# Sheet1.net
KiCad netlist of a schematic drawn in Altium Designer
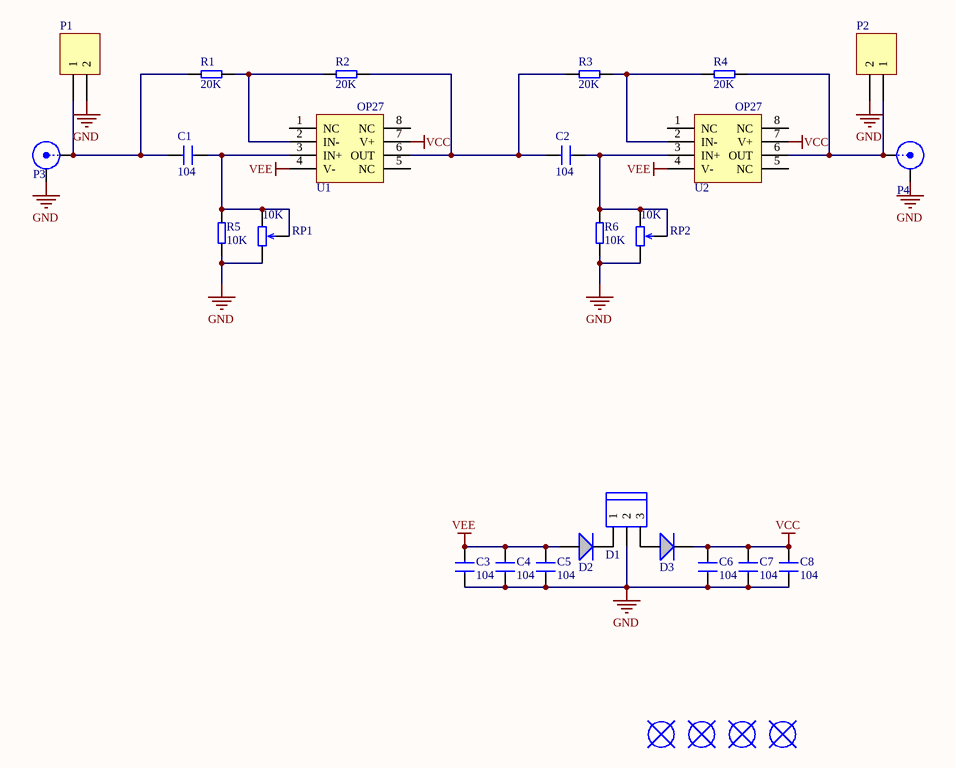
[diagram p0: 移相器Sheet1.SchDoc]

(export (version "E")
  (design (tool "Eeschema 10.0.6"))
  (components
    (comp (ref "C1") (value "104") (footprint "电容0805") (libsource (lib "自制元件库") (part "无极性电容")))
    (comp (ref "C2") (value "104") (footprint "电容0805") (libsource (lib "自制元件库") (part "无极性电容")))
    (comp (ref "C3") (value "104") (footprint "电容0805") (libsource (lib "自制元件库") (part "无极性电容")))
    (comp (ref "C4") (value "104") (footprint "电容0805") (libsource (lib "自制元件库") (part "无极性电容")))
    (comp (ref "C5") (value "104") (footprint "电容0805") (libsource (lib "自制元件库") (part "无极性电容")))
    (comp (ref "C6") (value "104") (footprint "电容0805") (libsource (lib "自制元件库") (part "无极性电容")))
    (comp (ref "C7") (value "104") (footprint "电容0805") (libsource (lib "自制元件库") (part "无极性电容")))
    (comp (ref "C8") (value "104") (footprint "电容0805") (libsource (lib "自制元件库") (part "无极性电容")))
    (comp (ref "D1") (value "接线端子") (footprint "CONN-TH_XH2.54-3P") (libsource (lib "自制元件库") (part "3P接线端子")))
    (comp (ref "D2") (value "1N4150") (footprint "DIOMELF3414N") (libsource (lib "自制元件库") (part "1N4150")))
    (comp (ref "D3") (value "1N4150") (footprint "DIOMELF3414N") (libsource (lib "自制元件库") (part "1N4150")))
    (comp (ref "G1") (value "定位孔") (footprint "定位孔") (libsource (lib "自制元件库") (part "定位孔")))
    (comp (ref "G2") (value "定位孔") (footprint "定位孔") (libsource (lib "自制元件库") (part "定位孔")))
    (comp (ref "G3") (value "定位孔") (footprint "定位孔") (libsource (lib "自制元件库") (part "定位孔")))
    (comp (ref "G4") (value "定位孔") (footprint "定位孔") (libsource (lib "自制元件库") (part "定位孔")))
    (comp (ref "P1")
      (value "Header 2")
      (footprint "HDR1X2")
      (description "Header, 2-Pin")
      (fields (field (name "PUBLISHER") "Altium Limited"))
      (libsource (lib "Miscellaneous Connectors") (part "Header 2"))
    )
    (comp (ref "P2")
      (value "Header 2")
      (footprint "HDR1X2")
      (description "Header, 2-Pin")
      (fields (field (name "PUBLISHER") "Altium Limited"))
      (libsource (lib "") (part "Header 2_1"))
    )
    (comp (ref "P3")
      (value "SMB")
      (footprint "BWSMA-KE-P001")
      (description "SMB Straight Connector")
      (fields (field (name "PUBLISHER") "Altium Limited"))
      (libsource (lib "自制元件库") (part "天线座"))
    )
    (comp (ref "P4")
      (value "SMB")
      (footprint "BWSMA-KE-P001")
      (description "SMB Straight Connector")
      (fields (field (name "PUBLISHER") "Altium Limited"))
      (libsource (lib "自制元件库") (part "天线座"))
    )
    (comp (ref "R1") (value "20K") (footprint "电阻0805") (libsource (lib "自制元件库") (part "电阻")))
    (comp (ref "R2") (value "20K") (footprint "电阻0805") (libsource (lib "自制元件库") (part "电阻")))
    (comp (ref "R3") (value "20K") (footprint "电阻0805") (libsource (lib "自制元件库") (part "电阻")))
    (comp (ref "R4") (value "20K") (footprint "电阻0805") (libsource (lib "自制元件库") (part "电阻")))
    (comp (ref "R5") (value "10K") (footprint "0805（两个串联式）") (libsource (lib "自制元件库") (part "电阻")))
    (comp (ref "R6") (value "10K") (footprint "0805（两个串联式）") (libsource (lib "自制元件库") (part "电阻")))
    (comp (ref "RP1") (value "10K") (footprint "电位器") (libsource (lib "自制元件库") (part "电位器")))
    (comp (ref "RP2") (value "10K") (footprint "电位器") (libsource (lib "自制元件库") (part "电位器")))
    (comp (ref "U1") (value "OP27") (footprint "SOIC-8") (libsource (lib "自制元件库") (part "OPA695")))
    (comp (ref "U2") (value "OP27") (footprint "SOIC-8") (libsource (lib "自制元件库") (part "OPA695")))
  )
  (nets
    (net (code "1") (name "GND") (class "Default")
      (node (ref "C3") (pin "1") (pinfunction "1_1") (pintype "passive"))
      (node (ref "C4") (pin "1") (pinfunction "1_1") (pintype "passive"))
      (node (ref "C5") (pin "1") (pinfunction "1_1") (pintype "passive"))
      (node (ref "C6") (pin "2") (pinfunction "2_2") (pintype "passive"))
      (node (ref "C7") (pin "2") (pinfunction "2_2") (pintype "passive"))
      (node (ref "C8") (pin "1") (pinfunction "1_1") (pintype "passive"))
      (node (ref "D1") (pin "2") (pinfunction "2_2") (pintype "passive"))
      (node (ref "P1") (pin "2") (pinfunction "2_2") (pintype "passive"))
      (node (ref "P2") (pin "2") (pinfunction "2_2") (pintype "passive"))
      (node (ref "P3") (pin "2") (pinfunction "Y_2") (pintype "passive"))
      (node (ref "P4") (pin "2") (pinfunction "Y_2") (pintype "passive"))
      (node (ref "R5") (pin "2") (pinfunction "2_2") (pintype "passive"))
      (node (ref "R6") (pin "2") (pinfunction "2_2") (pintype "passive"))
      (node (ref "RP1") (pin "3") (pinfunction "3_3") (pintype "passive"))
      (node (ref "RP2") (pin "3") (pinfunction "3_3") (pintype "passive"))
    )
    (net (code "2") (name "Net-(D1-Pad1)") (class "Default")
      (node (ref "D1") (pin "1") (pinfunction "1_1") (pintype "passive"))
      (node (ref "D2") (pin "2") (pinfunction "2_2") (pintype "passive"))
    )
    (net (code "3") (name "Net-(D1-Pad3)") (class "Default")
      (node (ref "D1") (pin "3") (pinfunction "3_3") (pintype "passive"))
      (node (ref "D3") (pin "1") (pinfunction "1_1") (pintype "passive"))
    )
    (net (code "4") (name "Net-(P3-X)") (class "Default")
      (node (ref "C1") (pin "2") (pinfunction "2_2") (pintype "passive"))
      (node (ref "P1") (pin "1") (pinfunction "1_1") (pintype "passive"))
      (node (ref "P3") (pin "1") (pinfunction "X_1") (pintype "passive"))
      (node (ref "R1") (pin "2") (pinfunction "2_2") (pintype "passive"))
    )
    (net (code "5") (name "Net-(P4-X)") (class "Default")
      (node (ref "P2") (pin "1") (pinfunction "1_1") (pintype "passive"))
      (node (ref "P4") (pin "1") (pinfunction "X_1") (pintype "passive"))
      (node (ref "R4") (pin "1") (pinfunction "1_1") (pintype "passive"))
      (node (ref "U2") (pin "6") (pinfunction "OUT_6") (pintype "passive"))
    )
    (net (code "6") (name "Net-(U1-IN+)") (class "Default")
      (node (ref "C1") (pin "1") (pinfunction "1_1") (pintype "passive"))
      (node (ref "R5") (pin "1") (pinfunction "1_1") (pintype "passive"))
      (node (ref "RP1") (pin "1") (pinfunction "1_1") (pintype "passive"))
      (node (ref "RP1") (pin "2") (pinfunction "2_2") (pintype "passive"))
      (node (ref "U1") (pin "3") (pinfunction "IN+_3") (pintype "passive"))
    )
    (net (code "7") (name "Net-(U1-IN-)") (class "Default")
      (node (ref "R1") (pin "1") (pinfunction "1_1") (pintype "passive"))
      (node (ref "R2") (pin "2") (pinfunction "2_2") (pintype "passive"))
      (node (ref "U1") (pin "2") (pinfunction "IN-_2") (pintype "passive"))
    )
    (net (code "8") (name "Net-(U1-OUT)") (class "Default")
      (node (ref "C2") (pin "2") (pinfunction "2_2") (pintype "passive"))
      (node (ref "R2") (pin "1") (pinfunction "1_1") (pintype "passive"))
      (node (ref "R3") (pin "2") (pinfunction "2_2") (pintype "passive"))
      (node (ref "U1") (pin "6") (pinfunction "OUT_6") (pintype "passive"))
    )
    (net (code "9") (name "Net-(U2-IN+)") (class "Default")
      (node (ref "C2") (pin "1") (pinfunction "1_1") (pintype "passive"))
      (node (ref "R6") (pin "1") (pinfunction "1_1") (pintype "passive"))
      (node (ref "RP2") (pin "1") (pinfunction "1_1") (pintype "passive"))
      (node (ref "RP2") (pin "2") (pinfunction "2_2") (pintype "passive"))
      (node (ref "U2") (pin "3") (pinfunction "IN+_3") (pintype "passive"))
    )
    (net (code "10") (name "Net-(U2-IN-)") (class "Default")
      (node (ref "R3") (pin "1") (pinfunction "1_1") (pintype "passive"))
      (node (ref "R4") (pin "2") (pinfunction "2_2") (pintype "passive"))
      (node (ref "U2") (pin "2") (pinfunction "IN-_2") (pintype "passive"))
    )
    (net (code "11") (name "VCC") (class "Default")
      (node (ref "C6") (pin "1") (pinfunction "1_1") (pintype "passive"))
      (node (ref "C7") (pin "1") (pinfunction "1_1") (pintype "passive"))
      (node (ref "C8") (pin "2") (pinfunction "2_2") (pintype "passive"))
      (node (ref "D3") (pin "2") (pinfunction "2_2") (pintype "passive"))
      (node (ref "U1") (pin "7") (pinfunction "V+_7") (pintype "passive"))
      (node (ref "U2") (pin "7") (pinfunction "V+_7") (pintype "passive"))
    )
    (net (code "12") (name "VEE") (class "Default")
      (node (ref "C3") (pin "2") (pinfunction "2_2") (pintype "passive"))
      (node (ref "C4") (pin "2") (pinfunction "2_2") (pintype "passive"))
      (node (ref "C5") (pin "2") (pinfunction "2_2") (pintype "passive"))
      (node (ref "D2") (pin "1") (pinfunction "1_1") (pintype "passive"))
      (node (ref "U1") (pin "4") (pinfunction "V-_4") (pintype "passive"))
      (node (ref "U2") (pin "4") (pinfunction "V-_4") (pintype "passive"))
    )
    (net (code "13") (name "unconnected-(U1-NC-Pad1)") (class "Default")
      (node (ref "U1") (pin "1") (pinfunction "NC_1") (pintype "passive"))
    )
    (net (code "14") (name "unconnected-(U1-NC-Pad5)") (class "Default")
      (node (ref "U1") (pin "5") (pinfunction "NC_5") (pintype "passive"))
    )
    (net (code "15") (name "unconnected-(U1-NC-Pad8)") (class "Default")
      (node (ref "U1") (pin "8") (pinfunction "NC_8") (pintype "passive"))
    )
    (net (code "16") (name "unconnected-(U2-NC-Pad1)") (class "Default")
      (node (ref "U2") (pin "1") (pinfunction "NC_1") (pintype "passive"))
    )
    (net (code "17") (name "unconnected-(U2-NC-Pad5)") (class "Default")
      (node (ref "U2") (pin "5") (pinfunction "NC_5") (pintype "passive"))
    )
    (net (code "18") (name "unconnected-(U2-NC-Pad8)") (class "Default")
      (node (ref "U2") (pin "8") (pinfunction "NC_8") (pintype "passive"))
    )
  )
)
